# SensorBoard.net
KiCad netlist of a schematic drawn in Altium Designer
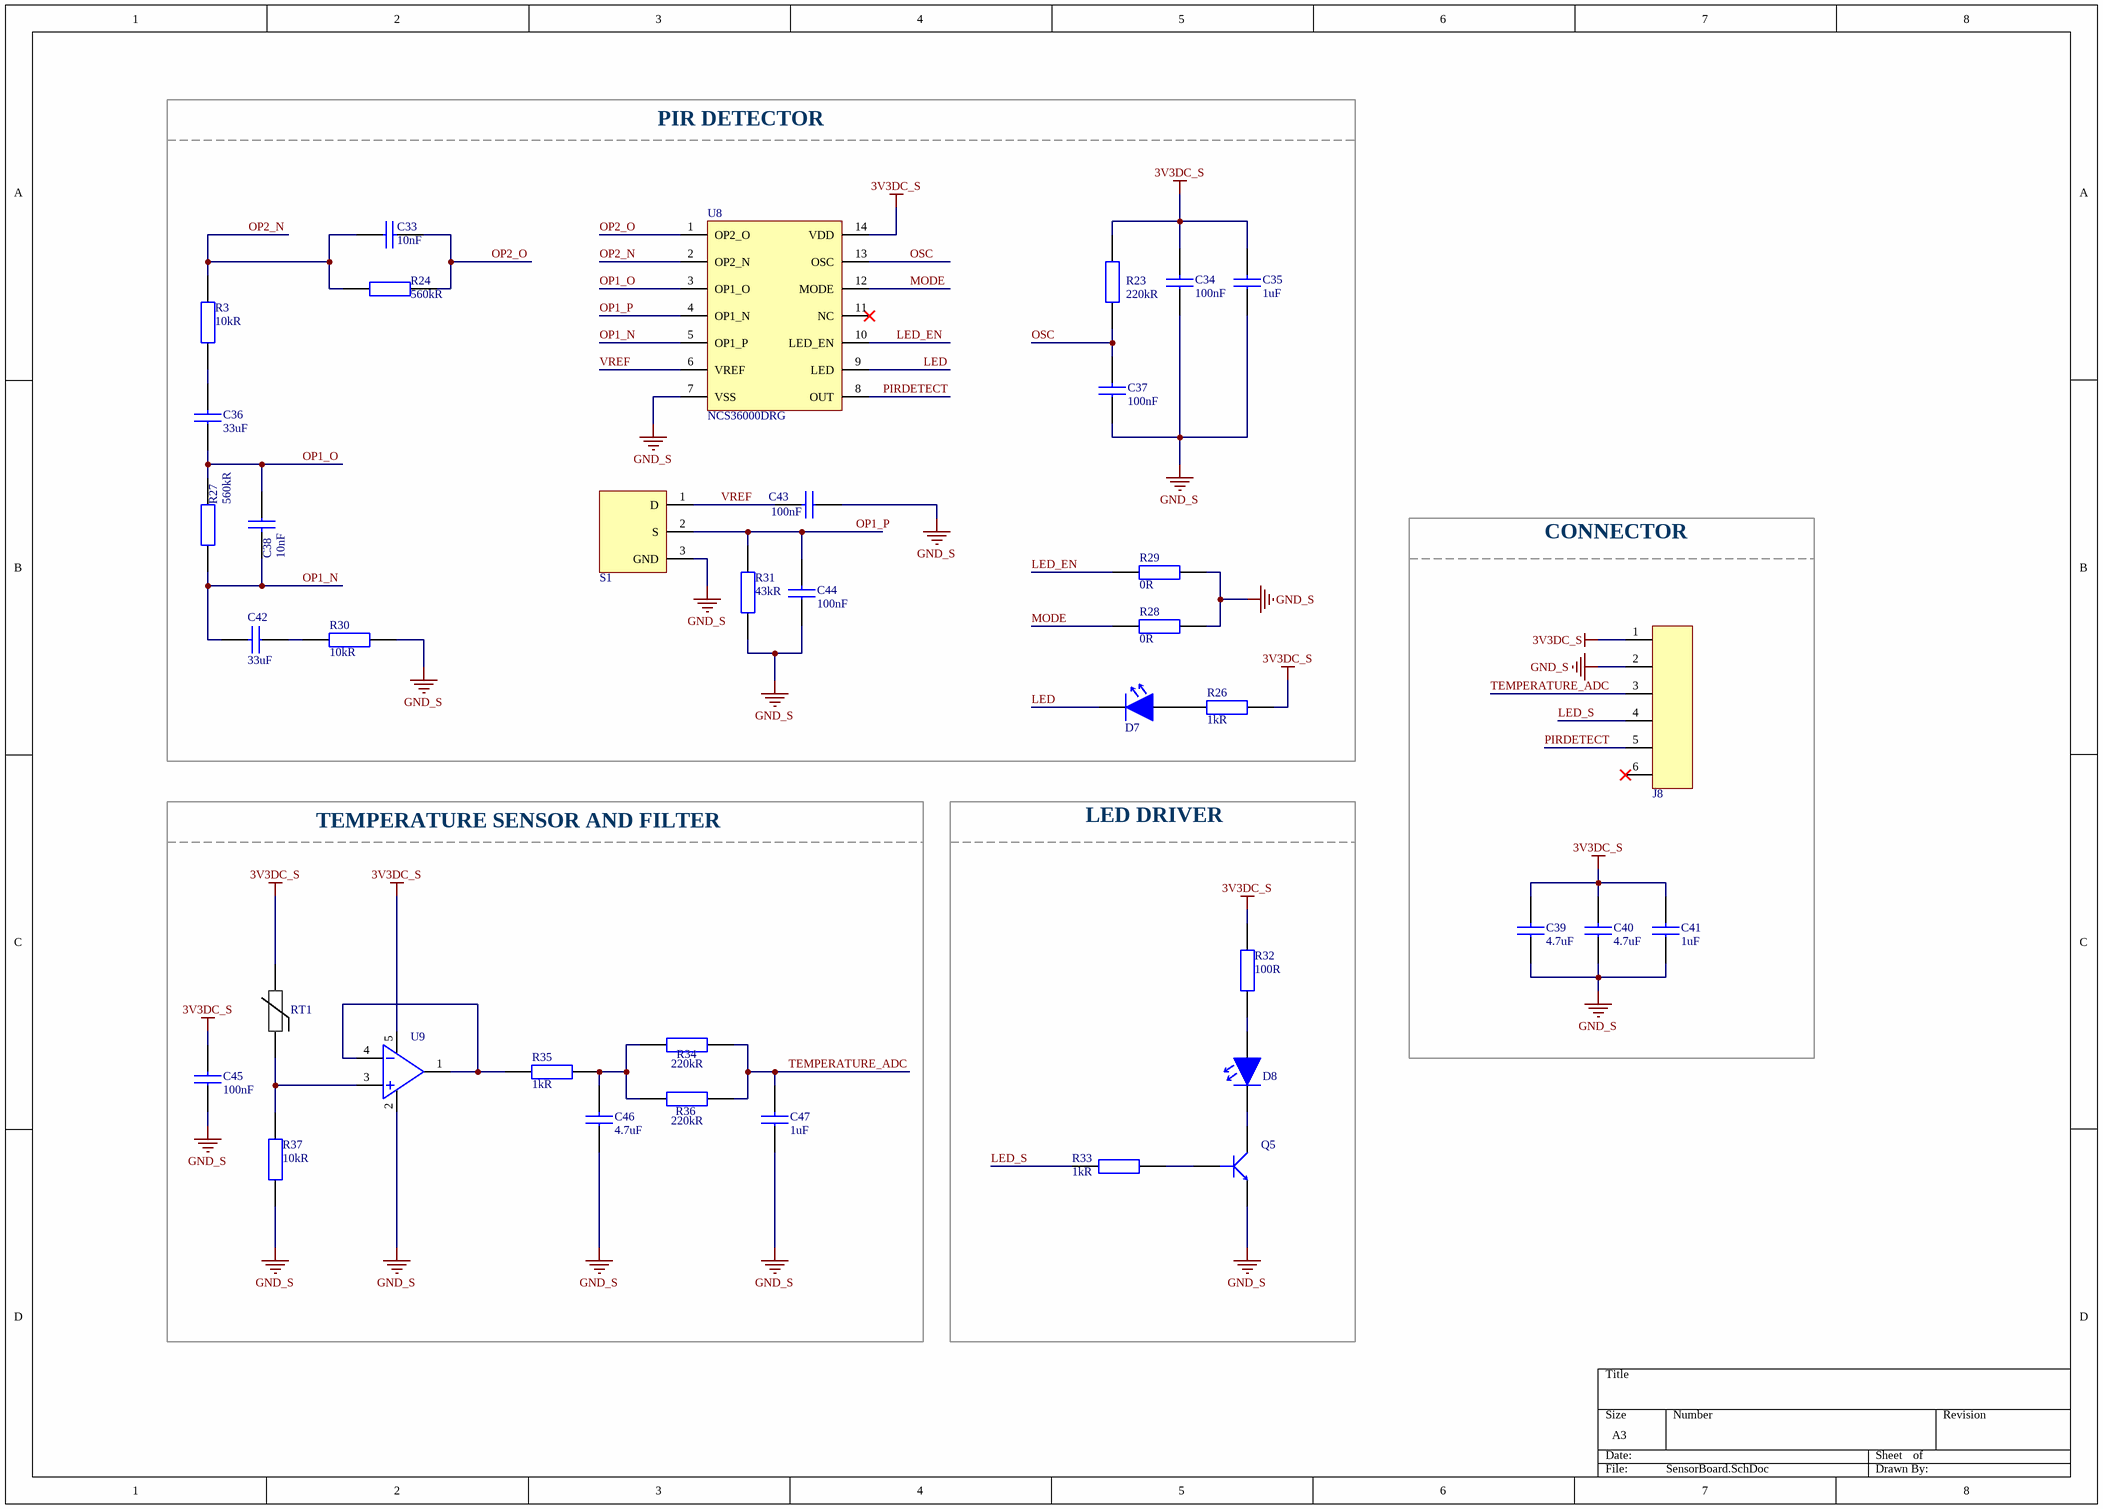
[diagram p0: SensorBoard.SchDoc]

(export (version "E")
  (design (tool "Eeschema 10.0.6"))
  (components
    (comp (ref "C33")
      (value "0603B103K160CT")
      (footprint "CAP_0603")
      (description "CAP CER 10nF %10 0603")
      (fields
        (field (name "MANUFACTURER") "Walsin Technologies")
        (field (name "TOLERANCE") "10%")
        (field (name "CAPACITANCE") "10nF")
        (field (name "DESIGNED BY") "BERK")
      )
      (libsource (lib "GuvenlikSistemi_Library") (part "CAP CER 10nF 0603"))
    )
    (comp (ref "C34")
      (value "C0603C104K5RACTU")
      (footprint "CAP_0603")
      (description "CAP CER 100nF %10 0603 SMD")
      (fields
        (field (name "MANUFACTURER") "KEMET")
        (field (name "TOLERANCE") "10%")
        (field (name "CAPACITANCE") "100nF")
        (field (name "DESIGNED BY") "BERK")
      )
      (libsource (lib "GuvenlikSistemi_Library") (part "CAP CER 100nF 0603"))
    )
    (comp (ref "C35")
      (value "CL21B105KBFNNNE")
      (footprint "CAP_0805")
      (description "CAP CER 1uF %10 0805")
      (fields
        (field (name "MANUFACTURER") "Samsung")
        (field (name "TOLERANCE") "10%")
        (field (name "CAPACITANCE") "1uF")
        (field (name "DESIGNED BY") "BERK")
      )
      (libsource (lib "GuvenlikSistemi_Library") (part "CAP CER 1uF 0805"))
    )
    (comp (ref "C36")
      (value "C3216X5R1E336M160AC")
      (footprint "CAP_1206")
      (description "CAP CER 33uF %20 1206 SMD")
      (fields
        (field (name "MANUFACTURER") "TDK")
        (field (name "TOLERANCE") "20%")
        (field (name "CAPACITANCE") "33uF")
        (field (name "DESIGNED BY") "BERK")
      )
      (libsource (lib "GuvenlikSistemi_Library") (part "CAP CER 33uF 1206"))
    )
    (comp (ref "C37")
      (value "C0603C104K5RACTU")
      (footprint "CAP_0603")
      (description "CAP CER 100nF %10 0603 SMD")
      (fields
        (field (name "MANUFACTURER") "KEMET")
        (field (name "TOLERANCE") "10%")
        (field (name "CAPACITANCE") "100nF")
        (field (name "DESIGNED BY") "BERK")
      )
      (libsource (lib "GuvenlikSistemi_Library") (part "CAP CER 100nF 0603"))
    )
    (comp (ref "C38")
      (value "0603B103K160CT")
      (footprint "CAP_0603")
      (description "CAP CER 10nF %10 0603")
      (fields
        (field (name "MANUFACTURER") "Walsin Technologies")
        (field (name "TOLERANCE") "10%")
        (field (name "CAPACITANCE") "10nF")
        (field (name "DESIGNED BY") "BERK")
      )
      (libsource (lib "GuvenlikSistemi_Library") (part "CAP CER 10nF 0603"))
    )
    (comp (ref "C39")
      (value "CL21A475KAQNNNE")
      (footprint "CAP_0805")
      (description "CAP CER 4.7uF %10 0805")
      (fields
        (field (name "MANUFACTURER") "Samsung")
        (field (name "TOLERANCE") "10%")
        (field (name "CAPACITANCE") "4.7uF")
        (field (name "DESIGNED BY") "BERK")
      )
      (libsource (lib "GuvenlikSistemi_Library") (part "CAP CER 4.7uF 0805"))
    )
    (comp (ref "C40")
      (value "CL21A475KAQNNNE")
      (footprint "CAP_0805")
      (description "CAP CER 4.7uF %10 0805")
      (fields
        (field (name "MANUFACTURER") "Samsung")
        (field (name "TOLERANCE") "10%")
        (field (name "CAPACITANCE") "4.7uF")
        (field (name "DESIGNED BY") "BERK")
      )
      (libsource (lib "GuvenlikSistemi_Library") (part "CAP CER 4.7uF 0805"))
    )
    (comp (ref "C41")
      (value "CL21B105KBFNNNE")
      (footprint "CAP_0805")
      (description "CAP CER 1uF %10 0805")
      (fields
        (field (name "MANUFACTURER") "Samsung")
        (field (name "TOLERANCE") "10%")
        (field (name "CAPACITANCE") "1uF")
        (field (name "DESIGNED BY") "BERK")
      )
      (libsource (lib "GuvenlikSistemi_Library") (part "CAP CER 1uF 0805"))
    )
    (comp (ref "C42")
      (value "C3216X5R1E336M160AC")
      (footprint "CAP_1206")
      (description "CAP CER 33uF %20 1206 SMD")
      (fields
        (field (name "MANUFACTURER") "TDK")
        (field (name "TOLERANCE") "20%")
        (field (name "CAPACITANCE") "33uF")
        (field (name "DESIGNED BY") "BERK")
      )
      (libsource (lib "GuvenlikSistemi_Library") (part "CAP CER 33uF 1206"))
    )
    (comp (ref "C43")
      (value "C0603C104K5RACTU")
      (footprint "CAP_0603")
      (description "CAP CER 100nF %10 0603 SMD")
      (fields
        (field (name "MANUFACTURER") "KEMET")
        (field (name "TOLERANCE") "10%")
        (field (name "CAPACITANCE") "100nF")
        (field (name "DESIGNED BY") "BERK")
      )
      (libsource (lib "GuvenlikSistemi_Library") (part "CAP CER 100nF 0603"))
    )
    (comp (ref "C44")
      (value "C0603C104K5RACTU")
      (footprint "CAP_0603")
      (description "CAP CER 100nF %10 0603 SMD")
      (fields
        (field (name "MANUFACTURER") "KEMET")
        (field (name "TOLERANCE") "10%")
        (field (name "CAPACITANCE") "100nF")
        (field (name "DESIGNED BY") "BERK")
      )
      (libsource (lib "GuvenlikSistemi_Library") (part "CAP CER 100nF 0603"))
    )
    (comp (ref "C45")
      (value "C0603C104K5RACTU")
      (footprint "CAP_0603")
      (description "CAP CER 100nF %10 0603 SMD")
      (fields
        (field (name "MANUFACTURER") "KEMET")
        (field (name "TOLERANCE") "10%")
        (field (name "CAPACITANCE") "100nF")
        (field (name "DESIGNED BY") "BERK")
      )
      (libsource (lib "GuvenlikSistemi_Library") (part "CAP CER 100nF 0603"))
    )
    (comp (ref "C46")
      (value "CL21A475KAQNNNE")
      (footprint "CAP_0805")
      (description "CAP CER 4.7uF %10 0805")
      (fields
        (field (name "MANUFACTURER") "Samsung")
        (field (name "TOLERANCE") "10%")
        (field (name "CAPACITANCE") "4.7uF")
        (field (name "DESIGNED BY") "BERK")
      )
      (libsource (lib "GuvenlikSistemi_Library") (part "CAP CER 4.7uF 0805"))
    )
    (comp (ref "C47")
      (value "CL21B105KBFNNNE")
      (footprint "CAP_0805")
      (description "CAP CER 1uF %10 0805")
      (fields
        (field (name "MANUFACTURER") "Samsung")
        (field (name "TOLERANCE") "10%")
        (field (name "CAPACITANCE") "1uF")
        (field (name "DESIGNED BY") "BERK")
      )
      (libsource (lib "GuvenlikSistemi_Library") (part "CAP CER 1uF 0805"))
    )
    (comp (ref "D7")
      (value "LTST-C171GKT")
      (footprint "LED_GREEN_0805")
      (description "Green 0805 130 º Min 5 mcd Typical 12 mcd Water Clear Lens SMT LED")
      (fields (field (name "MANUFACTURER") "Vishay Lite-On") (field (name "DESIGNED BY") "BERK"))
      (libsource (lib "GuvenlikSistemi_Library") (part "LED GREEN 0805"))
    )
    (comp (ref "D8")
      (value "LH R974-LP-1")
      (footprint "LED_RED_0805")
      (description "LED Uni-Color Hyper Red 660nm 2-Pin Chip 0805(2012Metric) T/R")
      (fields (field (name "MANUFACTURER") "Osram Opto") (field (name "DESIGNED BY") "BERK"))
      (libsource (lib "GuvenlikSistemi_Library") (part "LED RED 0805"))
    )
    (comp (ref "J8")
      (value "64800611622")
      (footprint "64800611622")
      (description "1.50mm 6PIN Connector")
      (fields (field (name "MANUFACTURER") "Wurth Electronics"))
      (libsource (lib "GuvenlikSistemi_Library") (part "64800611622_conn_6pin"))
    )
    (comp (ref "Q5")
      (value "MMBT3904-7-F")
      (footprint "SOT-23F")
      (description "Transistor General Purpose BJT NPN 40 Volt 0.2A Automotive 3-Pin SOT-23")
      (fields (field (name "MANUFACTURER") "Diodes Zetex") (field (name "DESIGNED BY") "BERK"))
      (libsource (lib "GuvenlikSistemi_Library") (part "MMBT3904-7-F"))
    )
    (comp (ref "R3")
      (value "RC0603FR-0710KL")
      (footprint "RES_0603")
      (description "RES 10K %1 OHM 0603 SMD")
      (fields
        (field (name "MANUFACTURER") "Yageo")
        (field (name "TOLERANCE") "1%")
        (field (name "RESISTANCE") "10kR")
        (field (name "DESIGNED BY") "BERK")
      )
      (libsource (lib "GuvenlikSistemi_Library") (part "RES 10K OHM 0603"))
    )
    (comp (ref "R23")
      (value "RC0603JR-07220KL")
      (footprint "RES_0603")
      (description "RES 220K %5 OHM 0603 SMD")
      (fields
        (field (name "MANUFACTURER") "Yageo")
        (field (name "TOLERANCE") "5%")
        (field (name "RESISTANCE") "220kR")
      )
      (libsource (lib "") (part "RES 220K OHM 0603_1"))
    )
    (comp (ref "R24")
      (value "RC0603JR-07560KL")
      (footprint "RES_0603")
      (description "RES SMD 560K OHM 5% 1/10W 0603")
      (fields
        (field (name "MANUFACTURER") "Yageo")
        (field (name "TOLERANCE") "5%")
        (field (name "RESISTANCE") "560kR")
        (field (name "DESIGNED BY") "BERK")
      )
      (libsource (lib "") (part "RES 560K OHM 0603_1"))
    )
    (comp (ref "R26")
      (value "RC0603FR-0710KL")
      (footprint "RES_0603")
      (description "RES 1K %1 OHM 0603 SMD")
      (fields
        (field (name "MANUFACTURER") "Yageo")
        (field (name "MANUFACTURER PART NUMBER") "RC0603JR-071KL")
        (field (name "RESISTANCE") "1kR")
        (field (name "DESIGNED BY") "BERK")
      )
      (libsource (lib "GuvenlikSistemi_Library") (part "RES 1K OHM 0603"))
    )
    (comp (ref "R27")
      (value "RC0603JR-07560KL")
      (footprint "RES_0603")
      (description "RES SMD 560K OHM 5% 1/10W 0603")
      (fields
        (field (name "MANUFACTURER") "Yageo")
        (field (name "TOLERANCE") "5%")
        (field (name "RESISTANCE") "560kR")
        (field (name "DESIGNED BY") "BERK")
      )
      (libsource (lib "GuvenlikSistemi_Library") (part "RES 560K OHM 0603"))
    )
    (comp (ref "R28")
      (value "RC0603JR-070RL")
      (footprint "RES_0603")
      (description "RES 0 %1 OHM 0603 SMD")
      (fields
        (field (name "MANUFACTURER") "Yageo")
        (field (name "TOLERANCE") "1%")
        (field (name "RESISTANCE") "0R")
        (field (name "DESIGNED BY") "BERK")
      )
      (libsource (lib "GuvenlikSistemi_Library") (part "RES 0 OHM 0603"))
    )
    (comp (ref "R29")
      (value "RC0603JR-070RL")
      (footprint "RES_0603")
      (description "RES 0 %1 OHM 0603 SMD")
      (fields
        (field (name "MANUFACTURER") "Yageo")
        (field (name "TOLERANCE") "1%")
        (field (name "RESISTANCE") "0R")
        (field (name "DESIGNED BY") "BERK")
      )
      (libsource (lib "GuvenlikSistemi_Library") (part "RES 0 OHM 0603"))
    )
    (comp (ref "R30")
      (value "RC0603FR-0710KL")
      (footprint "RES_0603")
      (description "RES 10K %1 OHM 0603 SMD")
      (fields
        (field (name "MANUFACTURER") "Yageo")
        (field (name "TOLERANCE") "1%")
        (field (name "RESISTANCE") "10kR")
        (field (name "DESIGNED BY") "BERK")
      )
      (libsource (lib "") (part "RES 10K OHM 0603_1"))
    )
    (comp (ref "R31")
      (value "RC0603JR-0743KL")
      (footprint "RES_0603")
      (description "RES 43K %5 OHM 0603 SMD")
      (fields
        (field (name "MANUFACTURER") "Yageo")
        (field (name "TOLERANCE") "5%")
        (field (name "RESISTANCE") "43kR")
        (field (name "DESIGNED BY") "BERK")
      )
      (libsource (lib "GuvenlikSistemi_Library") (part "RES 43K OHM 0603"))
    )
    (comp (ref "R32")
      (value "RC0603JR-07100RL")
      (footprint "RES_0603")
      (description "RES 100 %5 OHM 0603 SMD")
      (fields
        (field (name "MANUFACTURER") "Yageo")
        (field (name "TOLERANCE") "5%")
        (field (name "RESISTANCE") "100R")
        (field (name "DESIGNED BY") "BERK")
      )
      (libsource (lib "GuvenlikSistemi_Library") (part "RES 100 OHM 0603"))
    )
    (comp (ref "R33")
      (value "RC0603FR-0710KL")
      (footprint "RES_0603")
      (description "RES 1K %1 OHM 0603 SMD")
      (fields
        (field (name "MANUFACTURER") "Yageo")
        (field (name "MANUFACTURER PART NUMBER") "RC0603JR-071KL")
        (field (name "RESISTANCE") "1kR")
        (field (name "DESIGNED BY") "BERK")
      )
      (libsource (lib "GuvenlikSistemi_Library") (part "RES 1K OHM 0603"))
    )
    (comp (ref "R34")
      (value "RC0603JR-07220KL")
      (footprint "RES_0603")
      (description "RES 220K %5 OHM 0603 SMD")
      (fields
        (field (name "MANUFACTURER") "Yageo")
        (field (name "TOLERANCE") "5%")
        (field (name "RESISTANCE") "220kR")
      )
      (libsource (lib "GuvenlikSistemi_Library") (part "RES 220K OHM 0603"))
    )
    (comp (ref "R35")
      (value "RC0603FR-0710KL")
      (footprint "RES_0603")
      (description "RES 1K %1 OHM 0603 SMD")
      (fields
        (field (name "MANUFACTURER") "Yageo")
        (field (name "MANUFACTURER PART NUMBER") "RC0603JR-071KL")
        (field (name "RESISTANCE") "1kR")
        (field (name "DESIGNED BY") "BERK")
      )
      (libsource (lib "GuvenlikSistemi_Library") (part "RES 1K OHM 0603"))
    )
    (comp (ref "R36")
      (value "RC0603JR-07220KL")
      (footprint "RES_0603")
      (description "RES 220K %5 OHM 0603 SMD")
      (fields
        (field (name "MANUFACTURER") "Yageo")
        (field (name "TOLERANCE") "5%")
        (field (name "RESISTANCE") "220kR")
      )
      (libsource (lib "GuvenlikSistemi_Library") (part "RES 220K OHM 0603"))
    )
    (comp (ref "R37")
      (value "RC0603FR-0710KL")
      (footprint "RES_0603")
      (description "RES 10K %1 OHM 0603 SMD")
      (fields
        (field (name "MANUFACTURER") "Yageo")
        (field (name "TOLERANCE") "1%")
        (field (name "RESISTANCE") "10kR")
        (field (name "DESIGNED BY") "BERK")
      )
      (libsource (lib "GuvenlikSistemi_Library") (part "RES 10K OHM 0603"))
    )
    (comp (ref "RT1")
      (value "TFPT1206L1002FM")
      (footprint "RES_1206")
      (description "Thermistor PTC 10K Ohm 1% 1206")
      (fields
        (field (name "MANUFACTURER") "Vishay Dale")
        (field (name "TOLERANCE") "1%")
        (field (name "DESIGNED BY") "BERK")
      )
      (libsource (lib "GuvenlikSistemi_Library") (part "TFPT1206L1002FM"))
    )
    (comp (ref "S1")
      (value "LHI 878/3902")
      (footprint "LHI 878")
      (description "SENSOR PYRO DETECTOR DUAL MOTION")
      (fields (field (name "DESIGNED BY") "BERK"))
      (libsource (lib "GuvenlikSistemi_Library") (part "LHI 878/3902"))
    )
    (comp (ref "U8")
      (value "NCS36000DRG")
      (footprint "SOIC14")
      (description "PIR Controller Low Noise Amplifiers and LDO Regulator 14-Pin SOIC N T/R")
      (fields (field (name "MANUFACTURER") "ON Semiconductor") (field (name "DESIGNED BY") "BERK"))
      (libsource (lib "GuvenlikSistemi_Library") (part "NCS36000"))
    )
    (comp (ref "U9")
      (value "OPA314AIDBVR")
      (footprint "SOT23-5")
      (description "Op Amp OPA314")
      (fields (field (name "MANUFACTURER") "Texas Instruments") (field (name "DESIGNED BY") "BERK"))
      (libsource (lib "GuvenlikSistemi_Library") (part "OPA314"))
    )
  )
  (nets
    (net (code "1") (name "/LED") (class "Default")
      (node (ref "D7") (pin "1") (pinfunction "1_1") (pintype "power_in"))
      (node (ref "U8") (pin "9") (pinfunction "LED_9") (pintype "passive"))
    )
    (net (code "2") (name "/LED_EN") (class "Default")
      (node (ref "R29") (pin "2") (pinfunction "2_2") (pintype "passive"))
      (node (ref "U8") (pin "10") (pinfunction "LED_EN_10") (pintype "passive"))
    )
    (net (code "3") (name "/LED_S") (class "Default")
      (node (ref "J8") (pin "4") (pintype "power_in"))
      (node (ref "R33") (pin "1") (pinfunction "1_1") (pintype "passive"))
    )
    (net (code "4") (name "/MODE") (class "Default")
      (node (ref "R28") (pin "2") (pinfunction "2_2") (pintype "passive"))
      (node (ref "U8") (pin "12") (pinfunction "MODE_12") (pintype "passive"))
    )
    (net (code "5") (name "/OP1_N") (class "Default")
      (node (ref "C38") (pin "2") (pinfunction "2_2") (pintype "passive"))
      (node (ref "C42") (pin "2") (pinfunction "2_2") (pintype "passive"))
      (node (ref "R27") (pin "1") (pinfunction "1_1") (pintype "passive"))
      (node (ref "U8") (pin "5") (pinfunction "OP1_P_5") (pintype "passive"))
    )
    (net (code "6") (name "/OP1_O") (class "Default")
      (node (ref "C36") (pin "1") (pinfunction "1_1") (pintype "passive"))
      (node (ref "C38") (pin "1") (pinfunction "1_1") (pintype "passive"))
      (node (ref "R27") (pin "2") (pinfunction "2_2") (pintype "passive"))
      (node (ref "U8") (pin "3") (pinfunction "OP1_O_3") (pintype "passive"))
    )
    (net (code "7") (name "/OP1_P") (class "Default")
      (node (ref "C44") (pin "2") (pinfunction "2_2") (pintype "passive"))
      (node (ref "R31") (pin "2") (pinfunction "2_2") (pintype "passive"))
      (node (ref "S1") (pin "2") (pinfunction "S_2") (pintype "passive"))
      (node (ref "U8") (pin "4") (pinfunction "OP1_N_4") (pintype "passive"))
    )
    (net (code "8") (name "/OP2_N") (class "Default")
      (node (ref "C33") (pin "1") (pinfunction "1_1") (pintype "passive"))
      (node (ref "R24") (pin "1") (pinfunction "1_1") (pintype "passive"))
      (node (ref "R3") (pin "2") (pinfunction "2_2") (pintype "passive"))
      (node (ref "U8") (pin "2") (pinfunction "OP2_N_2") (pintype "passive"))
    )
    (net (code "9") (name "/OP2_O") (class "Default")
      (node (ref "C33") (pin "2") (pinfunction "2_2") (pintype "passive"))
      (node (ref "R24") (pin "2") (pinfunction "2_2") (pintype "passive"))
      (node (ref "U8") (pin "1") (pinfunction "OP2_O_1") (pintype "passive"))
    )
    (net (code "10") (name "/OSC") (class "Default")
      (node (ref "C37") (pin "2") (pinfunction "2_2") (pintype "passive"))
      (node (ref "R23") (pin "1") (pinfunction "1_1") (pintype "passive"))
      (node (ref "U8") (pin "13") (pinfunction "OSC_13") (pintype "passive"))
    )
    (net (code "11") (name "/PIRDETECT") (class "Default")
      (node (ref "J8") (pin "5") (pintype "power_in"))
      (node (ref "U8") (pin "8") (pinfunction "OUT_8") (pintype "passive"))
    )
    (net (code "12") (name "/TEMPERATURE_ADC") (class "Default")
      (node (ref "C47") (pin "2") (pinfunction "2_2") (pintype "passive"))
      (node (ref "J8") (pin "3") (pintype "power_in"))
      (node (ref "R34") (pin "2") (pinfunction "2_2") (pintype "passive"))
      (node (ref "R36") (pin "2") (pinfunction "2_2") (pintype "passive"))
    )
    (net (code "13") (name "/VREF") (class "Default")
      (node (ref "C43") (pin "2") (pinfunction "2_2") (pintype "passive"))
      (node (ref "S1") (pin "1") (pinfunction "D_1") (pintype "passive"))
      (node (ref "U8") (pin "6") (pinfunction "VREF_6") (pintype "passive"))
    )
    (net (code "14") (name "3V3DC_S") (class "Default")
      (node (ref "C34") (pin "2") (pinfunction "2_2") (pintype "passive"))
      (node (ref "C35") (pin "2") (pinfunction "2_2") (pintype "passive"))
      (node (ref "C39") (pin "2") (pinfunction "2_2") (pintype "passive"))
      (node (ref "C40") (pin "2") (pinfunction "2_2") (pintype "passive"))
      (node (ref "C41") (pin "2") (pinfunction "2_2") (pintype "passive"))
      (node (ref "C45") (pin "2") (pinfunction "2_2") (pintype "passive"))
      (node (ref "J8") (pin "1") (pintype "power_in"))
      (node (ref "R23") (pin "2") (pinfunction "2_2") (pintype "passive"))
      (node (ref "R26") (pin "2") (pinfunction "2_2") (pintype "passive"))
      (node (ref "R32") (pin "2") (pinfunction "2_2") (pintype "passive"))
      (node (ref "RT1") (pin "2") (pinfunction "2_2") (pintype "passive"))
      (node (ref "U8") (pin "14") (pinfunction "VDD_14") (pintype "passive"))
      (node (ref "U9") (pin "5") (pinfunction "5_5") (pintype "passive"))
    )
    (net (code "15") (name "GND_S") (class "Default")
      (node (ref "C34") (pin "1") (pinfunction "1_1") (pintype "passive"))
      (node (ref "C35") (pin "1") (pinfunction "1_1") (pintype "passive"))
      (node (ref "C37") (pin "1") (pinfunction "1_1") (pintype "passive"))
      (node (ref "C39") (pin "1") (pinfunction "1_1") (pintype "passive"))
      (node (ref "C40") (pin "1") (pinfunction "1_1") (pintype "passive"))
      (node (ref "C41") (pin "1") (pinfunction "1_1") (pintype "passive"))
      (node (ref "C43") (pin "1") (pinfunction "1_1") (pintype "passive"))
      (node (ref "C44") (pin "1") (pinfunction "1_1") (pintype "passive"))
      (node (ref "C45") (pin "1") (pinfunction "1_1") (pintype "passive"))
      (node (ref "C46") (pin "1") (pinfunction "1_1") (pintype "passive"))
      (node (ref "C47") (pin "1") (pinfunction "1_1") (pintype "passive"))
      (node (ref "J8") (pin "2") (pintype "power_in"))
      (node (ref "Q5") (pin "2") (pinfunction "E_2") (pintype "power_in"))
      (node (ref "R28") (pin "1") (pinfunction "1_1") (pintype "passive"))
      (node (ref "R29") (pin "1") (pinfunction "1_1") (pintype "passive"))
      (node (ref "R30") (pin "1") (pinfunction "1_1") (pintype "passive"))
      (node (ref "R31") (pin "1") (pinfunction "1_1") (pintype "passive"))
      (node (ref "R37") (pin "1") (pinfunction "1_1") (pintype "passive"))
      (node (ref "S1") (pin "3") (pinfunction "GND_3") (pintype "passive"))
      (node (ref "U8") (pin "7") (pinfunction "VSS_7") (pintype "passive"))
      (node (ref "U9") (pin "2") (pinfunction "2_2") (pintype "passive"))
    )
    (net (code "16") (name "Net-(C36-Pad2)") (class "Default")
      (node (ref "C36") (pin "2") (pinfunction "2_2") (pintype "passive"))
      (node (ref "R3") (pin "1") (pinfunction "1_1") (pintype "passive"))
    )
    (net (code "17") (name "Net-(C42-Pad1)") (class "Default")
      (node (ref "C42") (pin "1") (pinfunction "1_1") (pintype "passive"))
      (node (ref "R30") (pin "2") (pinfunction "2_2") (pintype "passive"))
    )
    (net (code "18") (name "Net-(C46-Pad2)") (class "Default")
      (node (ref "C46") (pin "2") (pinfunction "2_2") (pintype "passive"))
      (node (ref "R34") (pin "1") (pinfunction "1_1") (pintype "passive"))
      (node (ref "R35") (pin "2") (pinfunction "2_2") (pintype "passive"))
      (node (ref "R36") (pin "1") (pinfunction "1_1") (pintype "passive"))
    )
    (net (code "19") (name "Net-(D7-Pad2)") (class "Default")
      (node (ref "D7") (pin "2") (pinfunction "2_2") (pintype "power_in"))
      (node (ref "R26") (pin "1") (pinfunction "1_1") (pintype "passive"))
    )
    (net (code "20") (name "Net-(D8-Pad2)") (class "Default")
      (node (ref "D8") (pin "2") (pinfunction "2_2") (pintype "power_in"))
      (node (ref "R32") (pin "1") (pinfunction "1_1") (pintype "passive"))
    )
    (net (code "21") (name "Net-(Q5-B)") (class "Default")
      (node (ref "Q5") (pin "1") (pinfunction "B_1") (pintype "power_in"))
      (node (ref "R33") (pin "2") (pinfunction "2_2") (pintype "passive"))
    )
    (net (code "22") (name "Net-(Q5-C)") (class "Default")
      (node (ref "D8") (pin "1") (pinfunction "1_1") (pintype "power_in"))
      (node (ref "Q5") (pin "3") (pinfunction "C_3") (pintype "power_in"))
    )
    (net (code "23") (name "Net-(R35-Pad1)") (class "Default")
      (node (ref "R35") (pin "1") (pinfunction "1_1") (pintype "passive"))
      (node (ref "U9") (pin "1") (pinfunction "1_1") (pintype "passive"))
      (node (ref "U9") (pin "4") (pinfunction "4_4") (pintype "passive"))
    )
    (net (code "24") (name "Net-(R37-Pad2)") (class "Default")
      (node (ref "R37") (pin "2") (pinfunction "2_2") (pintype "passive"))
      (node (ref "RT1") (pin "1") (pinfunction "1_1") (pintype "passive"))
      (node (ref "U9") (pin "3") (pinfunction "3_3") (pintype "passive"))
    )
    (net (code "25") (name "unconnected-(J8-Pad6)") (class "Default")
      (node (ref "J8") (pin "6") (pintype "power_in+no_connect"))
    )
    (net (code "26") (name "unconnected-(U8-NC-Pad11)") (class "Default")
      (node (ref "U8") (pin "11") (pinfunction "NC_11") (pintype "passive+no_connect"))
    )
  )
)
